# FPGA_connector.net
KiCad netlist of a schematic drawn in Altium Designer
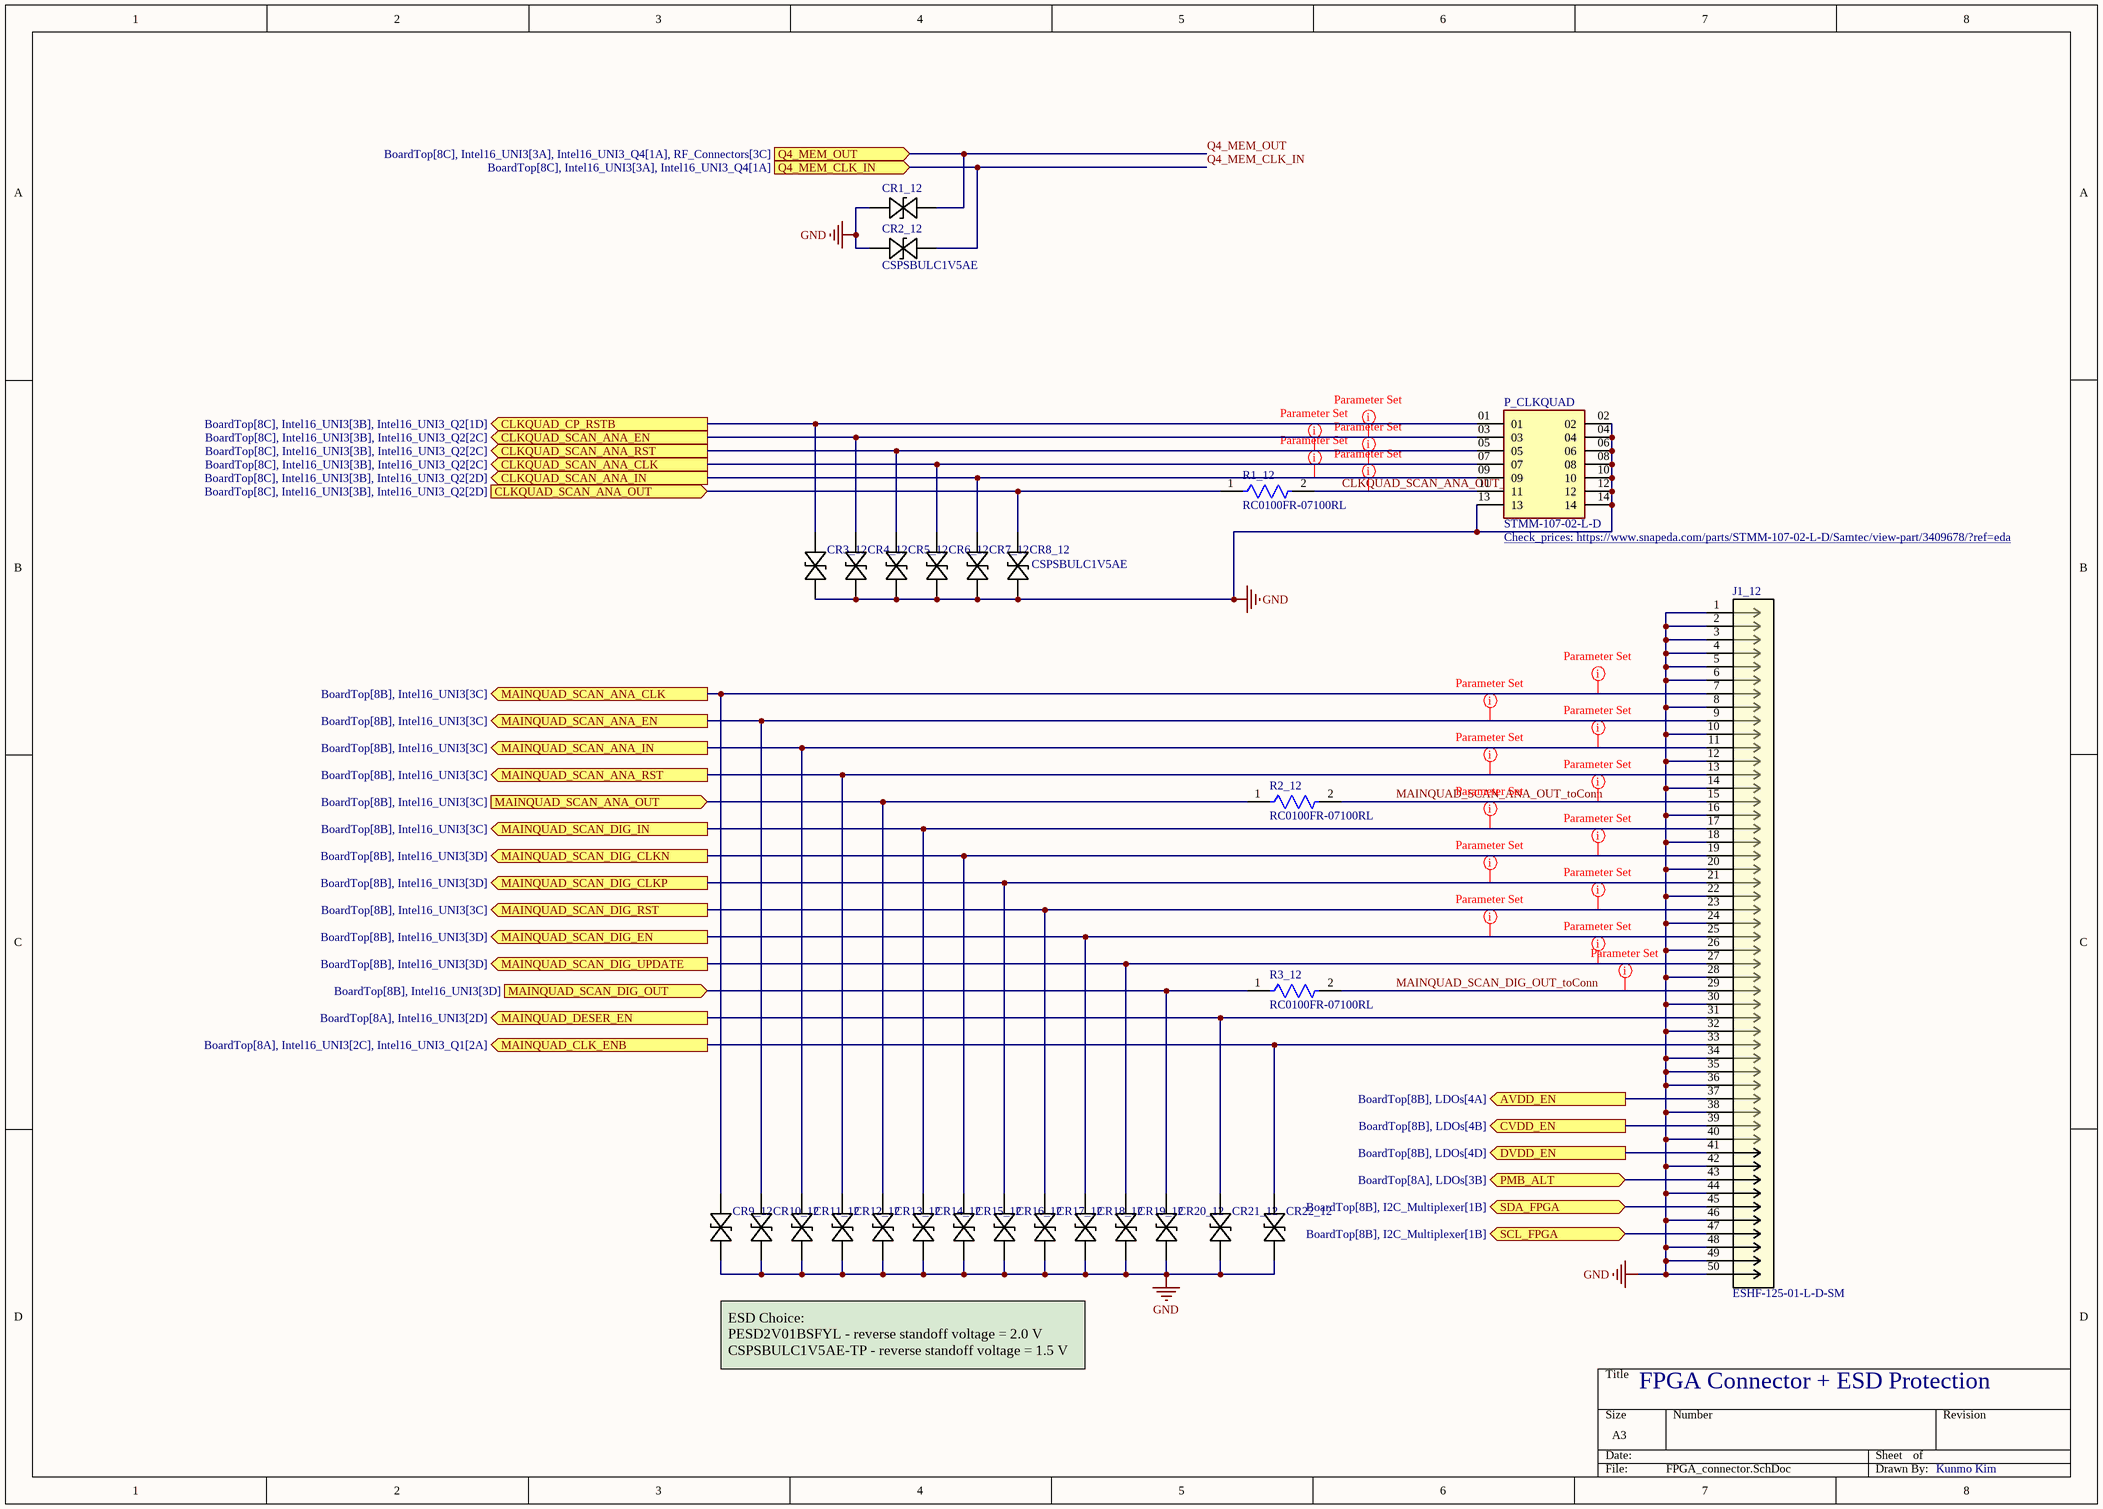
[diagram p0: FPGA_connector.SchDoc]

(export (version "E")
  (design (tool "Eeschema 10.0.6"))
  (components
    (comp (ref "CR1_12")
      (value "CSPSBULC1V5AE")
      (footprint "WLL-2-1_INF")
      (description "No Description Available")
      (libsource (lib "ESD108B1CSP0201XTSA1") (part "ESD108B1CSP0201XTSA1"))
    )
    (comp (ref "CR2_12")
      (value "CSPSBULC1V5AE")
      (footprint "WLL-2-1_INF")
      (description "No Description Available")
      (libsource (lib "ESD108B1CSP0201XTSA1") (part "ESD108B1CSP0201XTSA1"))
    )
    (comp (ref "CR3_12")
      (value "CSPSBULC1V5AE")
      (footprint "WLL-2-1_INF")
      (description "No Description Available")
      (libsource (lib "ESD108B1CSP0201XTSA1") (part "ESD108B1CSP0201XTSA1"))
    )
    (comp (ref "CR4_12")
      (value "CSPSBULC1V5AE")
      (footprint "WLL-2-1_INF")
      (description "No Description Available")
      (libsource (lib "ESD108B1CSP0201XTSA1") (part "ESD108B1CSP0201XTSA1"))
    )
    (comp (ref "CR5_12")
      (value "CSPSBULC1V5AE")
      (footprint "WLL-2-1_INF")
      (description "No Description Available")
      (libsource (lib "ESD108B1CSP0201XTSA1") (part "ESD108B1CSP0201XTSA1"))
    )
    (comp (ref "CR6_12")
      (value "CSPSBULC1V5AE")
      (footprint "WLL-2-1_INF")
      (description "No Description Available")
      (libsource (lib "ESD108B1CSP0201XTSA1") (part "ESD108B1CSP0201XTSA1"))
    )
    (comp (ref "CR7_12")
      (value "CSPSBULC1V5AE")
      (footprint "WLL-2-1_INF")
      (description "No Description Available")
      (libsource (lib "ESD108B1CSP0201XTSA1") (part "ESD108B1CSP0201XTSA1"))
    )
    (comp (ref "CR8_12")
      (value "CSPSBULC1V5AE")
      (footprint "WLL-2-1_INF")
      (description "No Description Available")
      (libsource (lib "ESD108B1CSP0201XTSA1") (part "ESD108B1CSP0201XTSA1"))
    )
    (comp (ref "CR9_12")
      (value "CSPSBULC1V5AE")
      (footprint "WLL-2-1_INF")
      (description "No Description Available")
      (libsource (lib "ESD108B1CSP0201XTSA1") (part "ESD108B1CSP0201XTSA1"))
    )
    (comp (ref "CR10_12")
      (value "CSPSBULC1V5AE")
      (footprint "WLL-2-1_INF")
      (description "No Description Available")
      (libsource (lib "ESD108B1CSP0201XTSA1") (part "ESD108B1CSP0201XTSA1"))
    )
    (comp (ref "CR11_12")
      (value "CSPSBULC1V5AE")
      (footprint "WLL-2-1_INF")
      (description "No Description Available")
      (libsource (lib "ESD108B1CSP0201XTSA1") (part "ESD108B1CSP0201XTSA1"))
    )
    (comp (ref "CR12_12")
      (value "CSPSBULC1V5AE")
      (footprint "WLL-2-1_INF")
      (description "No Description Available")
      (libsource (lib "ESD108B1CSP0201XTSA1") (part "ESD108B1CSP0201XTSA1"))
    )
    (comp (ref "CR13_12")
      (value "CSPSBULC1V5AE")
      (footprint "WLL-2-1_INF")
      (description "No Description Available")
      (libsource (lib "ESD108B1CSP0201XTSA1") (part "ESD108B1CSP0201XTSA1"))
    )
    (comp (ref "CR14_12")
      (value "CSPSBULC1V5AE")
      (footprint "WLL-2-1_INF")
      (description "No Description Available")
      (libsource (lib "ESD108B1CSP0201XTSA1") (part "ESD108B1CSP0201XTSA1"))
    )
    (comp (ref "CR15_12")
      (value "CSPSBULC1V5AE")
      (footprint "WLL-2-1_INF")
      (description "No Description Available")
      (libsource (lib "ESD108B1CSP0201XTSA1") (part "ESD108B1CSP0201XTSA1"))
    )
    (comp (ref "CR16_12")
      (value "CSPSBULC1V5AE")
      (footprint "WLL-2-1_INF")
      (description "No Description Available")
      (libsource (lib "ESD108B1CSP0201XTSA1") (part "ESD108B1CSP0201XTSA1"))
    )
    (comp (ref "CR17_12")
      (value "CSPSBULC1V5AE")
      (footprint "WLL-2-1_INF")
      (description "No Description Available")
      (libsource (lib "ESD108B1CSP0201XTSA1") (part "ESD108B1CSP0201XTSA1"))
    )
    (comp (ref "CR18_12")
      (value "CSPSBULC1V5AE")
      (footprint "WLL-2-1_INF")
      (description "No Description Available")
      (libsource (lib "ESD108B1CSP0201XTSA1") (part "ESD108B1CSP0201XTSA1"))
    )
    (comp (ref "CR19_12")
      (value "CSPSBULC1V5AE")
      (footprint "WLL-2-1_INF")
      (description "No Description Available")
      (libsource (lib "ESD108B1CSP0201XTSA1") (part "ESD108B1CSP0201XTSA1"))
    )
    (comp (ref "CR20_12")
      (value "CSPSBULC1V5AE")
      (footprint "WLL-2-1_INF")
      (description "No Description Available")
      (libsource (lib "ESD108B1CSP0201XTSA1") (part "ESD108B1CSP0201XTSA1"))
    )
    (comp (ref "CR21_12")
      (value "CSPSBULC1V5AE")
      (footprint "WLL-2-1_INF")
      (description "No Description Available")
      (libsource (lib "ESD108B1CSP0201XTSA1") (part "ESD108B1CSP0201XTSA1"))
    )
    (comp (ref "CR22_12")
      (value "CSPSBULC1V5AE")
      (footprint "WLL-2-1_INF")
      (description "No Description Available")
      (libsource (lib "ESD108B1CSP0201XTSA1") (part "ESD108B1CSP0201XTSA1"))
    )
    (comp (ref "J1_12")
      (value "ESHF-125-01-L-D-SM")
      (footprint "CONN_ESHF-125-01-x-D-SM_SAI")
      (description "No Description Available")
      (libsource (lib "FPGA_breakout_board") (part "ESHF-125-01-L-D-SM"))
    )
    (comp (ref "P_CLKQUAD")
      (value "STMM-107-02-L-D")
      (footprint "SAMTEC_STMM-107-02-L-D")
      (description "Connector Header Surface Mount 14 position 0.079 (2.00mm)")
      (fields
        (field (name "MF") "Samtec")
        (field (name "DIGI-KEY_PART_NUMBER") "STMM-107-02-L-D-SM-TR-ND")
        (field (name "CHECK_PRICES") "https://www.snapeda.com/parts/STMM-107-02-L-D/Samtec/view-part/3409678/?ref=eda")
      )
      (libsource (lib "STMM-107-02-L-D") (part "STMM-107-02-L-D"))
    )
    (comp (ref "R1_12")
      (value "RC0100FR-07100RL")
      (footprint "FP-RC0100-0_15-MFG")
      (description "RES SMD 100 OHM 1% 1/32W 01005")
      (fields (field (name "TOLERANCE") "1%"))
      (libsource (lib "yageo_01005_resistor") (part "yageo_100ohm"))
    )
    (comp (ref "R2_12")
      (value "RC0100FR-07100RL")
      (footprint "FP-RC0100-0_15-MFG")
      (description "RES SMD 100 OHM 1% 1/32W 01005")
      (fields (field (name "TOLERANCE") "1%"))
      (libsource (lib "yageo_01005_resistor") (part "yageo_100ohm"))
    )
    (comp (ref "R3_12")
      (value "RC0100FR-07100RL")
      (footprint "FP-RC0100-0_15-MFG")
      (description "RES SMD 100 OHM 1% 1/32W 01005")
      (fields (field (name "TOLERANCE") "1%"))
      (libsource (lib "yageo_01005_resistor") (part "yageo_100ohm"))
    )
  )
  (nets
    (net (code "1") (name "/AVDD_EN") (class "Default")
      (node (ref "J1_12") (pin "37") (pinfunction "37_37") (pintype "passive"))
    )
    (net (code "2") (name "/CLKQUAD_CP_RSTB") (class "Default")
      (node (ref "CR3_12") (pin "1") (pinfunction "1_1") (pintype "passive"))
      (node (ref "P_CLKQUAD") (pin "01") (pinfunction "01_01") (pintype "passive"))
    )
    (net (code "3") (name "/CLKQUAD_SCAN_ANA_CLK") (class "Default")
      (node (ref "CR6_12") (pin "1") (pinfunction "1_1") (pintype "passive"))
      (node (ref "P_CLKQUAD") (pin "07") (pinfunction "07_07") (pintype "passive"))
    )
    (net (code "4") (name "/CLKQUAD_SCAN_ANA_EN") (class "Default")
      (node (ref "CR4_12") (pin "1") (pinfunction "1_1") (pintype "passive"))
      (node (ref "P_CLKQUAD") (pin "03") (pinfunction "03_03") (pintype "passive"))
    )
    (net (code "5") (name "/CLKQUAD_SCAN_ANA_IN") (class "Default")
      (node (ref "CR7_12") (pin "1") (pinfunction "1_1") (pintype "passive"))
      (node (ref "P_CLKQUAD") (pin "09") (pinfunction "09_09") (pintype "passive"))
    )
    (net (code "6") (name "/CLKQUAD_SCAN_ANA_OUT") (class "Default")
      (node (ref "CR8_12") (pin "1") (pinfunction "1_1") (pintype "passive"))
      (node (ref "R1_12") (pin "1") (pinfunction "1_1") (pintype "passive"))
    )
    (net (code "7") (name "/CLKQUAD_SCAN_ANA_OUT_toConn") (class "Default")
      (node (ref "P_CLKQUAD") (pin "11") (pinfunction "11_11") (pintype "passive"))
      (node (ref "R1_12") (pin "2") (pinfunction "2_2") (pintype "passive"))
    )
    (net (code "8") (name "/CLKQUAD_SCAN_ANA_RST") (class "Default")
      (node (ref "CR5_12") (pin "1") (pinfunction "1_1") (pintype "passive"))
      (node (ref "P_CLKQUAD") (pin "05") (pinfunction "05_05") (pintype "passive"))
    )
    (net (code "9") (name "/CVDD_EN") (class "Default")
      (node (ref "J1_12") (pin "39") (pinfunction "39_39") (pintype "passive"))
    )
    (net (code "10") (name "/DVDD_EN") (class "Default")
      (node (ref "J1_12") (pin "41") (pinfunction "41_41") (pintype "passive"))
    )
    (net (code "11") (name "/MAINQUAD_CLK_ENB") (class "Default")
      (node (ref "CR22_12") (pin "1") (pinfunction "1_1") (pintype "passive"))
      (node (ref "J1_12") (pin "33") (pinfunction "33_33") (pintype "passive"))
    )
    (net (code "12") (name "/MAINQUAD_DESER_EN") (class "Default")
      (node (ref "CR21_12") (pin "1") (pinfunction "1_1") (pintype "passive"))
      (node (ref "J1_12") (pin "31") (pinfunction "31_31") (pintype "passive"))
    )
    (net (code "13") (name "/MAINQUAD_SCAN_ANA_CLK") (class "Default")
      (node (ref "CR9_12") (pin "1") (pinfunction "1_1") (pintype "passive"))
      (node (ref "J1_12") (pin "7") (pinfunction "7_7") (pintype "passive"))
    )
    (net (code "14") (name "/MAINQUAD_SCAN_ANA_EN") (class "Default")
      (node (ref "CR10_12") (pin "1") (pinfunction "1_1") (pintype "passive"))
      (node (ref "J1_12") (pin "9") (pinfunction "9_9") (pintype "passive"))
    )
    (net (code "15") (name "/MAINQUAD_SCAN_ANA_IN") (class "Default")
      (node (ref "CR11_12") (pin "1") (pinfunction "1_1") (pintype "passive"))
      (node (ref "J1_12") (pin "11") (pinfunction "11_11") (pintype "passive"))
    )
    (net (code "16") (name "/MAINQUAD_SCAN_ANA_OUT") (class "Default")
      (node (ref "CR13_12") (pin "1") (pinfunction "1_1") (pintype "passive"))
      (node (ref "R2_12") (pin "1") (pinfunction "1_1") (pintype "passive"))
    )
    (net (code "17") (name "/MAINQUAD_SCAN_ANA_OUT_toConn") (class "Default")
      (node (ref "J1_12") (pin "15") (pinfunction "15_15") (pintype "passive"))
      (node (ref "R2_12") (pin "2") (pinfunction "2_2") (pintype "passive"))
    )
    (net (code "18") (name "/MAINQUAD_SCAN_ANA_RST") (class "Default")
      (node (ref "CR12_12") (pin "1") (pinfunction "1_1") (pintype "passive"))
      (node (ref "J1_12") (pin "13") (pinfunction "13_13") (pintype "passive"))
    )
    (net (code "19") (name "/MAINQUAD_SCAN_DIG_CLKN") (class "Default")
      (node (ref "CR15_12") (pin "1") (pinfunction "1_1") (pintype "passive"))
      (node (ref "J1_12") (pin "19") (pinfunction "19_19") (pintype "passive"))
    )
    (net (code "20") (name "/MAINQUAD_SCAN_DIG_CLKP") (class "Default")
      (node (ref "CR16_12") (pin "1") (pinfunction "1_1") (pintype "passive"))
      (node (ref "J1_12") (pin "21") (pinfunction "21_21") (pintype "passive"))
    )
    (net (code "21") (name "/MAINQUAD_SCAN_DIG_EN") (class "Default")
      (node (ref "CR18_12") (pin "1") (pinfunction "1_1") (pintype "passive"))
      (node (ref "J1_12") (pin "25") (pinfunction "25_25") (pintype "passive"))
    )
    (net (code "22") (name "/MAINQUAD_SCAN_DIG_IN") (class "Default")
      (node (ref "CR14_12") (pin "1") (pinfunction "1_1") (pintype "passive"))
      (node (ref "J1_12") (pin "17") (pinfunction "17_17") (pintype "passive"))
    )
    (net (code "23") (name "/MAINQUAD_SCAN_DIG_OUT") (class "Default")
      (node (ref "CR20_12") (pin "1") (pinfunction "1_1") (pintype "passive"))
      (node (ref "R3_12") (pin "1") (pinfunction "1_1") (pintype "passive"))
    )
    (net (code "24") (name "/MAINQUAD_SCAN_DIG_OUT_toConn") (class "Default")
      (node (ref "J1_12") (pin "29") (pinfunction "29_29") (pintype "passive"))
      (node (ref "R3_12") (pin "2") (pinfunction "2_2") (pintype "passive"))
    )
    (net (code "25") (name "/MAINQUAD_SCAN_DIG_RST") (class "Default")
      (node (ref "CR17_12") (pin "1") (pinfunction "1_1") (pintype "passive"))
      (node (ref "J1_12") (pin "23") (pinfunction "23_23") (pintype "passive"))
    )
    (net (code "26") (name "/MAINQUAD_SCAN_DIG_UPDATE") (class "Default")
      (node (ref "CR19_12") (pin "1") (pinfunction "1_1") (pintype "passive"))
      (node (ref "J1_12") (pin "27") (pinfunction "27_27") (pintype "passive"))
    )
    (net (code "27") (name "/PMB_ALT") (class "Default")
      (node (ref "J1_12") (pin "43") (pinfunction "43_43") (pintype "passive"))
    )
    (net (code "28") (name "/Q4_MEM_CLK_IN") (class "Default")
      (node (ref "CR2_12") (pin "2") (pinfunction "2_2") (pintype "passive"))
    )
    (net (code "29") (name "/Q4_MEM_OUT") (class "Default")
      (node (ref "CR1_12") (pin "2") (pinfunction "2_2") (pintype "passive"))
    )
    (net (code "30") (name "/SCL_FPGA") (class "Default")
      (node (ref "J1_12") (pin "47") (pinfunction "47_47") (pintype "passive"))
    )
    (net (code "31") (name "/SDA_FPGA") (class "Default")
      (node (ref "J1_12") (pin "45") (pinfunction "45_45") (pintype "passive"))
    )
    (net (code "32") (name "GND") (class "Default")
      (node (ref "CR10_12") (pin "2") (pinfunction "2_2") (pintype "passive"))
      (node (ref "CR11_12") (pin "2") (pinfunction "2_2") (pintype "passive"))
      (node (ref "CR12_12") (pin "2") (pinfunction "2_2") (pintype "passive"))
      (node (ref "CR13_12") (pin "2") (pinfunction "2_2") (pintype "passive"))
      (node (ref "CR14_12") (pin "2") (pinfunction "2_2") (pintype "passive"))
      (node (ref "CR15_12") (pin "2") (pinfunction "2_2") (pintype "passive"))
      (node (ref "CR16_12") (pin "2") (pinfunction "2_2") (pintype "passive"))
      (node (ref "CR17_12") (pin "2") (pinfunction "2_2") (pintype "passive"))
      (node (ref "CR18_12") (pin "2") (pinfunction "2_2") (pintype "passive"))
      (node (ref "CR19_12") (pin "2") (pinfunction "2_2") (pintype "passive"))
      (node (ref "CR1_12") (pin "1") (pinfunction "1_1") (pintype "passive"))
      (node (ref "CR20_12") (pin "2") (pinfunction "2_2") (pintype "passive"))
      (node (ref "CR21_12") (pin "2") (pinfunction "2_2") (pintype "passive"))
      (node (ref "CR22_12") (pin "2") (pinfunction "2_2") (pintype "passive"))
      (node (ref "CR2_12") (pin "1") (pinfunction "1_1") (pintype "passive"))
      (node (ref "CR3_12") (pin "2") (pinfunction "2_2") (pintype "passive"))
      (node (ref "CR4_12") (pin "2") (pinfunction "2_2") (pintype "passive"))
      (node (ref "CR5_12") (pin "2") (pinfunction "2_2") (pintype "passive"))
      (node (ref "CR6_12") (pin "2") (pinfunction "2_2") (pintype "passive"))
      (node (ref "CR7_12") (pin "2") (pinfunction "2_2") (pintype "passive"))
      (node (ref "CR8_12") (pin "2") (pinfunction "2_2") (pintype "passive"))
      (node (ref "CR9_12") (pin "2") (pinfunction "2_2") (pintype "passive"))
      (node (ref "J1_12") (pin "1") (pinfunction "1_1") (pintype "passive"))
      (node (ref "J1_12") (pin "10") (pinfunction "10_10") (pintype "passive"))
      (node (ref "J1_12") (pin "12") (pinfunction "12_12") (pintype "passive"))
      (node (ref "J1_12") (pin "14") (pinfunction "14_14") (pintype "passive"))
      (node (ref "J1_12") (pin "16") (pinfunction "16_16") (pintype "passive"))
      (node (ref "J1_12") (pin "18") (pinfunction "18_18") (pintype "passive"))
      (node (ref "J1_12") (pin "2") (pinfunction "2_2") (pintype "passive"))
      (node (ref "J1_12") (pin "20") (pinfunction "20_20") (pintype "passive"))
      (node (ref "J1_12") (pin "22") (pinfunction "22_22") (pintype "passive"))
      (node (ref "J1_12") (pin "24") (pinfunction "24_24") (pintype "passive"))
      (node (ref "J1_12") (pin "26") (pinfunction "26_26") (pintype "passive"))
      (node (ref "J1_12") (pin "28") (pinfunction "28_28") (pintype "passive"))
      (node (ref "J1_12") (pin "3") (pinfunction "3_3") (pintype "passive"))
      (node (ref "J1_12") (pin "30") (pinfunction "30_30") (pintype "passive"))
      (node (ref "J1_12") (pin "32") (pinfunction "32_32") (pintype "passive"))
      (node (ref "J1_12") (pin "34") (pinfunction "34_34") (pintype "passive"))
      (node (ref "J1_12") (pin "35") (pinfunction "35_35") (pintype "passive"))
      (node (ref "J1_12") (pin "36") (pinfunction "36_36") (pintype "passive"))
      (node (ref "J1_12") (pin "38") (pinfunction "38_38") (pintype "passive"))
      (node (ref "J1_12") (pin "4") (pinfunction "4_4") (pintype "passive"))
      (node (ref "J1_12") (pin "40") (pinfunction "40_40") (pintype "passive"))
      (node (ref "J1_12") (pin "42") (pinfunction "42_42") (pintype "passive"))
      (node (ref "J1_12") (pin "44") (pinfunction "44_44") (pintype "passive"))
      (node (ref "J1_12") (pin "46") (pinfunction "46_46") (pintype "passive"))
      (node (ref "J1_12") (pin "48") (pinfunction "48_48") (pintype "passive"))
      (node (ref "J1_12") (pin "49") (pinfunction "49_49") (pintype "passive"))
      (node (ref "J1_12") (pin "5") (pinfunction "5_5") (pintype "passive"))
      (node (ref "J1_12") (pin "50") (pinfunction "50_50") (pintype "passive"))
      (node (ref "J1_12") (pin "6") (pinfunction "6_6") (pintype "passive"))
      (node (ref "J1_12") (pin "8") (pinfunction "8_8") (pintype "passive"))
      (node (ref "P_CLKQUAD") (pin "02") (pinfunction "02_02") (pintype "passive"))
      (node (ref "P_CLKQUAD") (pin "04") (pinfunction "04_04") (pintype "passive"))
      (node (ref "P_CLKQUAD") (pin "06") (pinfunction "06_06") (pintype "passive"))
      (node (ref "P_CLKQUAD") (pin "08") (pinfunction "08_08") (pintype "passive"))
      (node (ref "P_CLKQUAD") (pin "10") (pinfunction "10_10") (pintype "passive"))
      (node (ref "P_CLKQUAD") (pin "12") (pinfunction "12_12") (pintype "passive"))
      (node (ref "P_CLKQUAD") (pin "13") (pinfunction "13_13") (pintype "passive"))
      (node (ref "P_CLKQUAD") (pin "14") (pinfunction "14_14") (pintype "passive"))
    )
  )
)
